# 08_GPS.net
KiCad netlist of a schematic drawn in Altium Designer
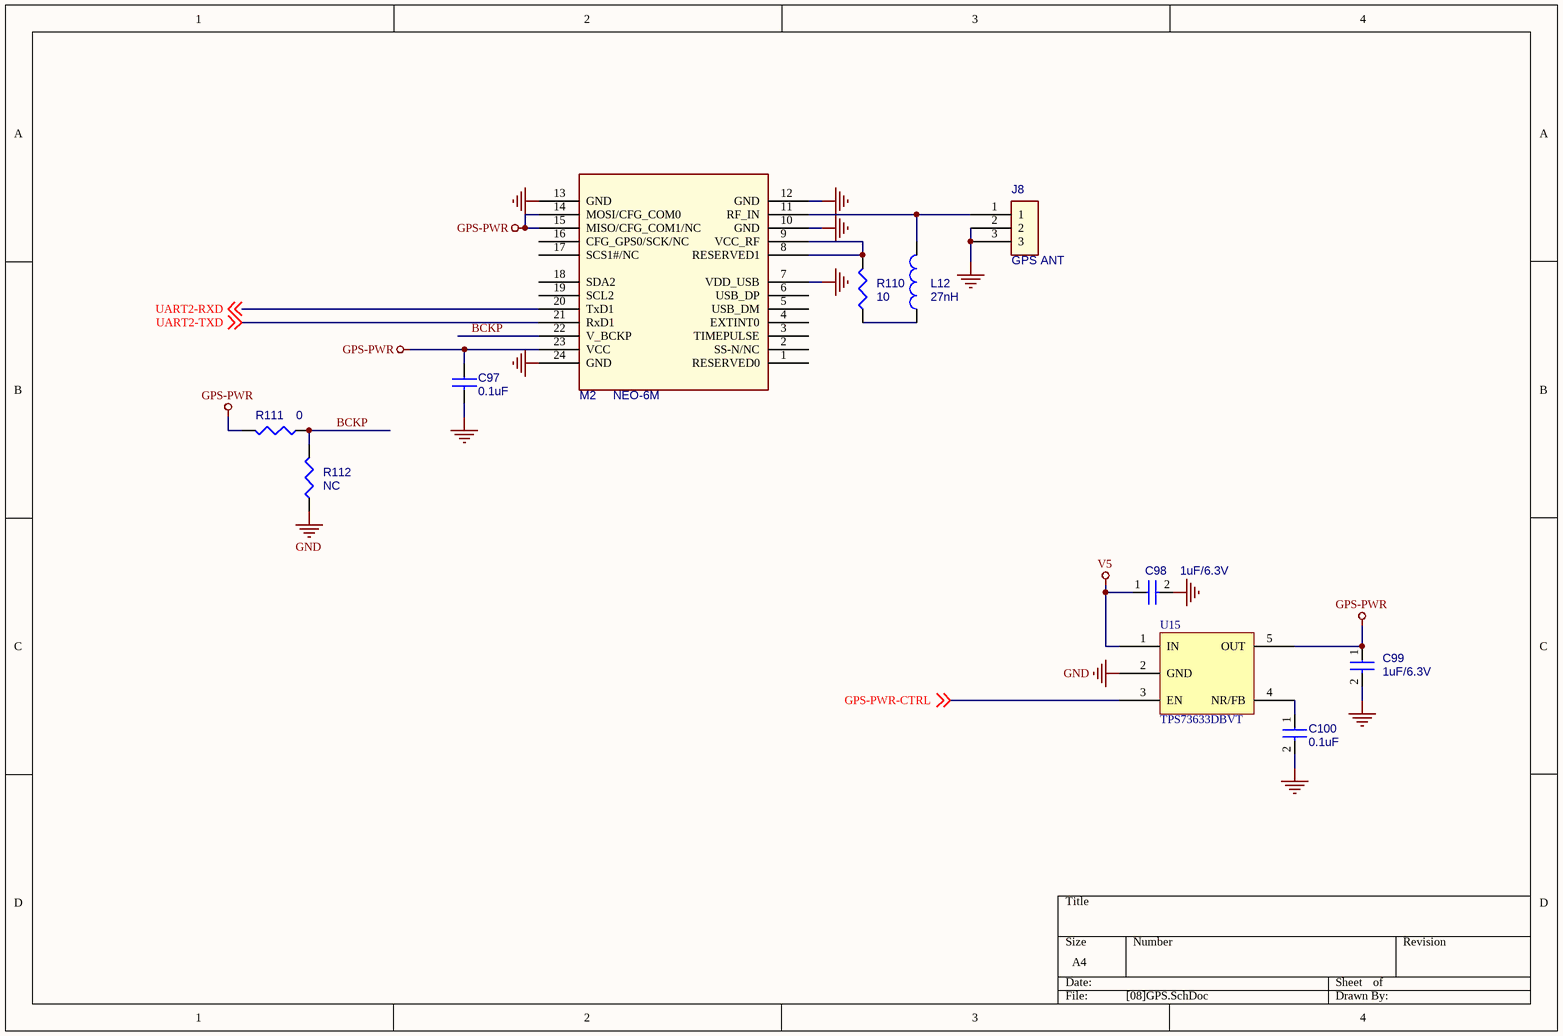
[diagram p0: [08]GPS.SchDoc]

(export (version "E")
  (design (tool "Eeschema 10.0.6"))
  (components
    (comp (ref "C97") (value "0.1uF") (libsource (lib "*") (part "P_CAP NP")))
    (comp (ref "C98") (value "1uF/6.3V") (libsource (lib "*") (part "CAP NP_Dup2")))
    (comp (ref "C99") (value "1uF/6.3V") (libsource (lib "*") (part "CAP NP_Dup2")))
    (comp (ref "C100") (value "0.1uF") (libsource (lib "*") (part "CAP NP_Dup2")))
    (comp (ref "J8") (value "GPS ANT") (footprint "ANT") (libsource (lib "*") (part "HRS_U_0.FL-R-SMT-10")))
    (comp (ref "L12")
      (value "27nH")
      (footprint "0603")
      (libsource (lib "*") (part "2.2UH_LPS3015-222MLC_1.5A_20%~D"))
    )
    (comp (ref "M2") (value "NEO-6M") (footprint "NEO-6") (libsource (lib "*") (part "NEO-5M")))
    (comp (ref "R110") (value "10") (footprint "0603") (libsource (lib "*") (part "P_R")))
    (comp (ref "R111") (value "0") (footprint "0603") (libsource (lib "*") (part "P_R")))
    (comp (ref "R112") (value "NC") (footprint "0603") (libsource (lib "*") (part "P_R")))
    (comp (ref "U15")
      (value "TPS73633DBVT")
      (footprint "SOT23-5")
      (libsource (lib "Schlib") (part "TPS73633DBVT"))
    )
  )
  (nets
    (net (code "1") (name "/BCKP") (class "Default")
      (node (ref "M2") (pin "22") (pinfunction "V_BCKP_22") (pintype "passive"))
      (node (ref "R111") (pin "1") (pinfunction "1_1") (pintype "passive"))
      (node (ref "R112") (pin "2") (pinfunction "2_2") (pintype "passive"))
    )
    (net (code "2") (name "GND") (class "Default")
      (node (ref "C100") (pin "2") (pinfunction "2_2") (pintype "passive"))
      (node (ref "C97") (pin "2") (pinfunction "2_2") (pintype "passive"))
      (node (ref "C98") (pin "2") (pinfunction "2_2") (pintype "passive"))
      (node (ref "C99") (pin "2") (pinfunction "2_2") (pintype "passive"))
      (node (ref "J8") (pin "2") (pinfunction "2_2") (pintype "passive"))
      (node (ref "J8") (pin "3") (pinfunction "3_3") (pintype "passive"))
      (node (ref "M2") (pin "10") (pinfunction "GND_10") (pintype "power_in"))
      (node (ref "M2") (pin "12") (pinfunction "GND_12") (pintype "power_in"))
      (node (ref "M2") (pin "13") (pinfunction "GND_13") (pintype "power_in"))
      (node (ref "M2") (pin "24") (pinfunction "GND_24") (pintype "power_in"))
      (node (ref "M2") (pin "7") (pinfunction "VDD_USB_7") (pintype "passive"))
      (node (ref "R112") (pin "1") (pinfunction "1_1") (pintype "passive"))
      (node (ref "U15") (pin "2") (pinfunction "GND_2") (pintype "passive"))
    )
    (net (code "3") (name "GPS-PWR") (class "Default")
      (node (ref "C97") (pin "1") (pinfunction "1_1") (pintype "passive"))
      (node (ref "C99") (pin "1") (pinfunction "1_1") (pintype "passive"))
      (node (ref "M2") (pin "14") (pinfunction "MOSI/CFG_COM0_14") (pintype "passive"))
      (node (ref "M2") (pin "15") (pinfunction "MISO/CFG_COM1/NC_15") (pintype "passive"))
      (node (ref "M2") (pin "23") (pinfunction "VCC_23") (pintype "passive"))
      (node (ref "R111") (pin "2") (pinfunction "2_2") (pintype "passive"))
      (node (ref "U15") (pin "5") (pinfunction "OUT_5") (pintype "passive"))
    )
    (net (code "4") (name "GPS-PWR-CTRL") (class "Default")
      (node (ref "U15") (pin "3") (pinfunction "EN_3") (pintype "passive"))
    )
    (net (code "5") (name "Net-(L12-Pad1)") (class "Default")
      (node (ref "L12") (pin "1") (pinfunction "1_1") (pintype "passive"))
      (node (ref "R110") (pin "1") (pinfunction "1_1") (pintype "passive"))
    )
    (net (code "6") (name "Net-(M2-RESERVED1)") (class "Default")
      (node (ref "M2") (pin "8") (pinfunction "RESERVED1_8") (pintype "passive"))
      (node (ref "M2") (pin "9") (pinfunction "VCC_RF_9") (pintype "passive"))
      (node (ref "R110") (pin "2") (pinfunction "2_2") (pintype "passive"))
    )
    (net (code "7") (name "Net-(M2-RF_IN)") (class "Default")
      (node (ref "J8") (pin "1") (pinfunction "1_1") (pintype "passive"))
      (node (ref "L12") (pin "2") (pinfunction "2_2") (pintype "passive"))
      (node (ref "M2") (pin "11") (pinfunction "RF_IN_11") (pintype "passive"))
    )
    (net (code "8") (name "Net-(U15-NR{slash}FB)") (class "Default")
      (node (ref "C100") (pin "1") (pinfunction "1_1") (pintype "passive"))
      (node (ref "U15") (pin "4") (pinfunction "NR/FB_4") (pintype "passive"))
    )
    (net (code "9") (name "UART2-RXD") (class "Default")
      (node (ref "M2") (pin "20") (pinfunction "TxD1_20") (pintype "passive"))
    )
    (net (code "10") (name "UART2-TXD") (class "Default")
      (node (ref "M2") (pin "21") (pinfunction "RxD1_21") (pintype "passive"))
    )
    (net (code "11") (name "V5") (class "Default")
      (node (ref "C98") (pin "1") (pinfunction "1_1") (pintype "passive"))
      (node (ref "U15") (pin "1") (pinfunction "IN_1") (pintype "passive"))
    )
    (net (code "12") (name "unconnected-(M2-CFG_GPS0{slash}SCK{slash}NC-Pad16)") (class "Default")
      (node (ref "M2") (pin "16") (pinfunction "CFG_GPS0/SCK/NC_16") (pintype "passive"))
    )
    (net (code "13") (name "unconnected-(M2-EXTINT0-Pad4)") (class "Default")
      (node (ref "M2") (pin "4") (pinfunction "EXTINT0_4") (pintype "passive"))
    )
    (net (code "14") (name "unconnected-(M2-RESERVED0-Pad1)") (class "Default")
      (node (ref "M2") (pin "1") (pinfunction "RESERVED0_1") (pintype "passive"))
    )
    (net (code "15") (name "unconnected-(M2-SCL2-Pad19)") (class "Default")
      (node (ref "M2") (pin "19") (pinfunction "SCL2_19") (pintype "passive"))
    )
    (net (code "16") (name "unconnected-(M2-SCS1#{slash}NC-Pad17)") (class "Default")
      (node (ref "M2") (pin "17") (pinfunction "SCS1#/NC_17") (pintype "passive"))
    )
    (net (code "17") (name "unconnected-(M2-SDA2-Pad18)") (class "Default")
      (node (ref "M2") (pin "18") (pinfunction "SDA2_18") (pintype "passive"))
    )
    (net (code "18") (name "unconnected-(M2-SS-N{slash}NC-Pad2)") (class "Default")
      (node (ref "M2") (pin "2") (pinfunction "SS-N/NC_2") (pintype "passive"))
    )
    (net (code "19") (name "unconnected-(M2-TIMEPULSE-Pad3)") (class "Default")
      (node (ref "M2") (pin "3") (pinfunction "TIMEPULSE_3") (pintype "passive"))
    )
    (net (code "20") (name "unconnected-(M2-USB_DM-Pad5)") (class "Default")
      (node (ref "M2") (pin "5") (pinfunction "USB_DM_5") (pintype "passive"))
    )
    (net (code "21") (name "unconnected-(M2-USB_DP-Pad6)") (class "Default")
      (node (ref "M2") (pin "6") (pinfunction "USB_DP_6") (pintype "passive"))
    )
  )
)
